# TxFrontendWaveyRadar.net
KiCad netlist of a schematic drawn in Altium Designer
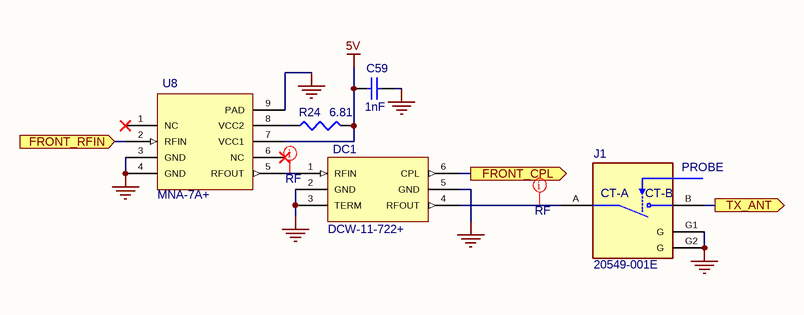
[diagram p0: TxFrontendWaveyRadar.SchDoc]

(export (version "E")
  (design (tool "Eeschema 10.0.6"))
  (components
    (comp (ref "C59")
      (value "1nF")
      (footprint "CAPC0402(1005)33_L")
      (description "Chip Capacitor, 1nF +/-20%, 50V, 0402, Thickness 0.33 mm")
      (fields (field (name "TOLERANCE") "10%") (field (name "Comment") "Capacitor 1nF +/-20% 50V 0402"))
      (libsource (lib "University of South Florida") (part "CAP-NP-2"))
    )
    (comp (ref "DC1")
      (value "DCW-11-722+")
      (footprint "DCW-11-722+-Footprint-1")
      (description "50 ohm 11dB directional coupler 2.4 to 7.2 GHz")
      (libsource (lib "University of South Florida") (part "DCW-11-722+"))
    )
    (comp (ref "J1")
      (value "20549-001E")
      (footprint "IPEX_20549-001E")
      (fields (field (name "MF") "I-PEX"))
      (libsource (lib "University of South Florida") (part "20549-001E"))
    )
    (comp (ref "R24")
      (value "6.81")
      (footprint "RESC1005X40X25NL05T05")
      (description "CRCW Series 0402 0.063 W 6.81 Ohm ±1 % ±100 ppm/K SMT Thick Film Chip Resistor")
      (fields (field (name "Comment") "CRCW04026R81FKED"))
      (libsource (lib "University of South Florida") (part "ResistorSymbol"))
    )
    (comp (ref "U8")
      (value "MNA-7A+")
      (footprint "DQ849")
      (description "50 ohm 1.5 to 6GHz 17.4db amplifier")
      (libsource (lib "University of South Florida") (part "MNA-7A+"))
    )
  )
  (nets
    (net (code "1") (name "/FRONT_CPL") (class "Default")
      (node (ref "DC1") (pin "6") (pinfunction "CPL_6") (pintype "output"))
    )
    (net (code "2") (name "/FRONT_RFIN") (class "Default")
      (node (ref "U8") (pin "2") (pinfunction "RFIN_2") (pintype "input"))
    )
    (net (code "3") (name "/TX_ANT") (class "Default")
      (node (ref "J1") (pin "B") (pinfunction "CT-B_B") (pintype "passive"))
    )
    (net (code "4") (name "5V") (class "Default")
      (node (ref "C59") (pin "2") (pinfunction "2_2") (pintype "passive"))
      (node (ref "R24") (pin "2") (pinfunction "2_2") (pintype "passive"))
      (node (ref "U8") (pin "7") (pinfunction "VCC1_7") (pintype "power_in"))
    )
    (net (code "5") (name "GND") (class "Default")
      (node (ref "C59") (pin "1") (pinfunction "1_1") (pintype "passive"))
      (node (ref "DC1") (pin "2") (pinfunction "GND_2") (pintype "power_in"))
      (node (ref "DC1") (pin "3") (pinfunction "TERM_3") (pintype "passive"))
      (node (ref "DC1") (pin "5") (pinfunction "GND_5") (pintype "power_in"))
      (node (ref "J1") (pin "G1") (pinfunction "G_G1") (pintype "power_in"))
      (node (ref "J1") (pin "G2") (pinfunction "G_G2") (pintype "power_in"))
      (node (ref "U8") (pin "3") (pinfunction "GND_3") (pintype "power_in"))
      (node (ref "U8") (pin "4") (pinfunction "GND_4") (pintype "power_in"))
      (node (ref "U8") (pin "9") (pinfunction "PAD_9") (pintype "power_in"))
    )
    (net (code "6") (name "Net-(DC1-RFIN)") (class "Default")
      (node (ref "DC1") (pin "1") (pinfunction "RFIN_1") (pintype "input"))
      (node (ref "U8") (pin "5") (pinfunction "RFOUT_5") (pintype "output"))
    )
    (net (code "7") (name "Net-(DC1-RFOUT)") (class "Default")
      (node (ref "DC1") (pin "4") (pinfunction "RFOUT_4") (pintype "output"))
      (node (ref "J1") (pin "A") (pinfunction "CT-A_A") (pintype "passive"))
    )
    (net (code "8") (name "Net-(U8-VCC2)") (class "Default")
      (node (ref "R24") (pin "1") (pinfunction "1_1") (pintype "passive"))
      (node (ref "U8") (pin "8") (pinfunction "VCC2_8") (pintype "power_in"))
    )
    (net (code "9") (name "unconnected-(U8-NC-Pad1)") (class "Default")
      (node (ref "U8") (pin "1") (pinfunction "NC_1") (pintype "passive+no_connect"))
    )
    (net (code "10") (name "unconnected-(U8-NC-Pad6)") (class "Default")
      (node (ref "U8") (pin "6") (pinfunction "NC_6") (pintype "passive+no_connect"))
    )
  )
)
